# tssop14.net
KiCad netlist of a schematic drawn in EAGLE
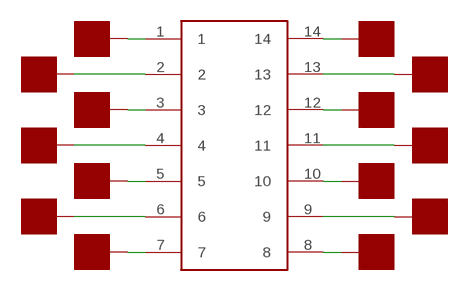
[diagram p0: schematic, sheet 1]

(export (version "E")
  (design (tool "Eeschema 10.0.6"))
  (components
    (comp (ref "IC1")
      (value "TSSOP14")
      (footprint "eagle-import:TSSOP14")
      (libsource (lib "eagle-import") (part "TSSOP14"))
    )
    (comp (ref "U$1")
      (value "PAD50MIL")
      (footprint "eagle-import:PAD_50MIL")
      (libsource (lib "eagle-import") (part "PAD50MIL"))
    )
    (comp (ref "U$2")
      (value "PAD50MIL")
      (footprint "eagle-import:PAD_50MIL")
      (libsource (lib "eagle-import") (part "PAD50MIL"))
    )
    (comp (ref "U$3")
      (value "PAD50MIL")
      (footprint "eagle-import:PAD_50MIL")
      (libsource (lib "eagle-import") (part "PAD50MIL"))
    )
    (comp (ref "U$4")
      (value "PAD50MIL")
      (footprint "eagle-import:PAD_50MIL")
      (libsource (lib "eagle-import") (part "PAD50MIL"))
    )
    (comp (ref "U$5")
      (value "PAD50MIL")
      (footprint "eagle-import:PAD_50MIL")
      (libsource (lib "eagle-import") (part "PAD50MIL"))
    )
    (comp (ref "U$6")
      (value "PAD50MIL")
      (footprint "eagle-import:PAD_50MIL")
      (libsource (lib "eagle-import") (part "PAD50MIL"))
    )
    (comp (ref "U$7")
      (value "PAD50MIL")
      (footprint "eagle-import:PAD_50MIL")
      (libsource (lib "eagle-import") (part "PAD50MIL"))
    )
    (comp (ref "U$8")
      (value "PAD50MIL")
      (footprint "eagle-import:PAD_50MIL")
      (libsource (lib "eagle-import") (part "PAD50MIL"))
    )
    (comp (ref "U$9")
      (value "PAD50MIL")
      (footprint "eagle-import:PAD_50MIL")
      (libsource (lib "eagle-import") (part "PAD50MIL"))
    )
    (comp (ref "U$10")
      (value "PAD50MIL")
      (footprint "eagle-import:PAD_50MIL")
      (libsource (lib "eagle-import") (part "PAD50MIL"))
    )
    (comp (ref "U$11")
      (value "PAD50MIL")
      (footprint "eagle-import:PAD_50MIL")
      (libsource (lib "eagle-import") (part "PAD50MIL"))
    )
    (comp (ref "U$12")
      (value "PAD50MIL")
      (footprint "eagle-import:PAD_50MIL")
      (libsource (lib "eagle-import") (part "PAD50MIL"))
    )
    (comp (ref "U$13")
      (value "PAD50MIL")
      (footprint "eagle-import:PAD_50MIL")
      (libsource (lib "eagle-import") (part "PAD50MIL"))
    )
    (comp (ref "U$14")
      (value "PAD50MIL")
      (footprint "eagle-import:PAD_50MIL")
      (libsource (lib "eagle-import") (part "PAD50MIL"))
    )
  )
  (nets
    (net (code "1") (name "Net-(IC1-Pad1)") (class "Default")
      (node (ref "IC1") (pin "1") (pinfunction "1_1") (pintype "bidirectional"))
      (node (ref "U$8") (pin "P$1") (pinfunction "P$1_P$1") (pintype "bidirectional"))
    )
    (net (code "2") (name "Net-(IC1-Pad2)") (class "Default")
      (node (ref "IC1") (pin "2") (pinfunction "2_2") (pintype "bidirectional"))
      (node (ref "U$9") (pin "P$1") (pinfunction "P$1_P$1") (pintype "bidirectional"))
    )
    (net (code "3") (name "Net-(IC1-Pad3)") (class "Default")
      (node (ref "IC1") (pin "3") (pinfunction "3_3") (pintype "bidirectional"))
      (node (ref "U$10") (pin "P$1") (pinfunction "P$1_P$1") (pintype "bidirectional"))
    )
    (net (code "4") (name "Net-(IC1-Pad4)") (class "Default")
      (node (ref "IC1") (pin "4") (pinfunction "4_4") (pintype "bidirectional"))
      (node (ref "U$11") (pin "P$1") (pinfunction "P$1_P$1") (pintype "bidirectional"))
    )
    (net (code "5") (name "Net-(IC1-Pad5)") (class "Default")
      (node (ref "IC1") (pin "5") (pinfunction "5_5") (pintype "bidirectional"))
      (node (ref "U$12") (pin "P$1") (pinfunction "P$1_P$1") (pintype "bidirectional"))
    )
    (net (code "6") (name "Net-(IC1-Pad6)") (class "Default")
      (node (ref "IC1") (pin "6") (pinfunction "6_6") (pintype "bidirectional"))
      (node (ref "U$13") (pin "P$1") (pinfunction "P$1_P$1") (pintype "bidirectional"))
    )
    (net (code "7") (name "Net-(IC1-Pad7)") (class "Default")
      (node (ref "IC1") (pin "7") (pinfunction "7_7") (pintype "bidirectional"))
      (node (ref "U$14") (pin "P$1") (pinfunction "P$1_P$1") (pintype "bidirectional"))
    )
    (net (code "8") (name "Net-(IC1-Pad8)") (class "Default")
      (node (ref "IC1") (pin "8") (pinfunction "8_8") (pintype "bidirectional"))
      (node (ref "U$7") (pin "P$1") (pinfunction "P$1_P$1") (pintype "bidirectional"))
    )
    (net (code "9") (name "Net-(IC1-Pad9)") (class "Default")
      (node (ref "IC1") (pin "9") (pinfunction "9_9") (pintype "bidirectional"))
      (node (ref "U$6") (pin "P$1") (pinfunction "P$1_P$1") (pintype "bidirectional"))
    )
    (net (code "10") (name "Net-(IC1-Pad10)") (class "Default")
      (node (ref "IC1") (pin "10") (pinfunction "10_10") (pintype "bidirectional"))
      (node (ref "U$5") (pin "P$1") (pinfunction "P$1_P$1") (pintype "bidirectional"))
    )
    (net (code "11") (name "Net-(IC1-Pad11)") (class "Default")
      (node (ref "IC1") (pin "11") (pinfunction "11_11") (pintype "bidirectional"))
      (node (ref "U$4") (pin "P$1") (pinfunction "P$1_P$1") (pintype "bidirectional"))
    )
    (net (code "12") (name "Net-(IC1-Pad12)") (class "Default")
      (node (ref "IC1") (pin "12") (pinfunction "12_12") (pintype "bidirectional"))
      (node (ref "U$3") (pin "P$1") (pinfunction "P$1_P$1") (pintype "bidirectional"))
    )
    (net (code "13") (name "Net-(IC1-Pad13)") (class "Default")
      (node (ref "IC1") (pin "13") (pinfunction "13_13") (pintype "bidirectional"))
      (node (ref "U$2") (pin "P$1") (pinfunction "P$1_P$1") (pintype "bidirectional"))
    )
    (net (code "14") (name "Net-(IC1-Pad14)") (class "Default")
      (node (ref "IC1") (pin "14") (pinfunction "14_14") (pintype "bidirectional"))
      (node (ref "U$1") (pin "P$1") (pinfunction "P$1_P$1") (pintype "bidirectional"))
    )
  )
)
